# 5V_DCDC_XL7035.net
KiCad netlist of a schematic drawn in EAGLE
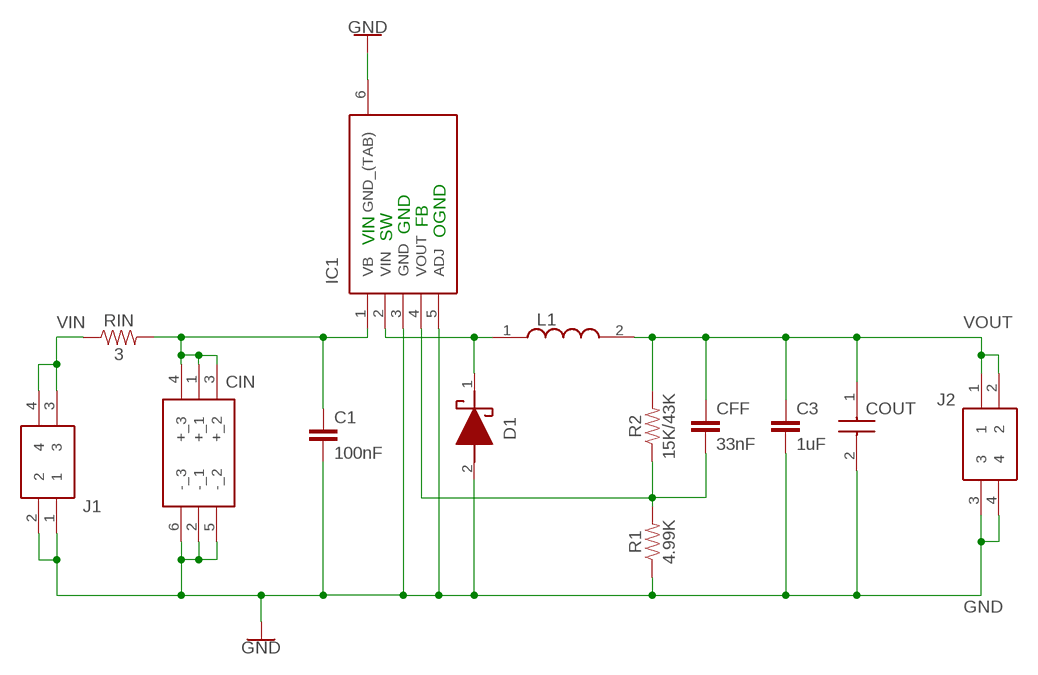
[diagram p0: schematic, sheet 1]

(export (version "E")
  (design (tool "Eeschema 10.0.6"))
  (components
    (comp (ref "C1")
      (value "100nF")
      (footprint "eagle-import:0603")
      (libsource (lib "eagle-import") (part "CAP-0603"))
    )
    (comp (ref "C3")
      (value "1uF")
      (footprint "eagle-import:0603")
      (libsource (lib "eagle-import") (part "CAP-0603"))
    )
    (comp (ref "CFF")
      (value "33nF")
      (footprint "eagle-import:0603")
      (libsource (lib "eagle-import") (part "CAP-0603"))
    )
    (comp (ref "CIN")
      (value "EEE-FK1K101AV")
      (footprint "eagle-import:EEEFK0J332AV")
      (fields (field (name "MOUSER_PART_NUMBER") "667-EEE-FK1K101AV"))
      (libsource (lib "eagle-import") (part "EEE-FK1K101AV"))
    )
    (comp (ref "COUT")
      (value "EMK325ABJ107MM-T")
      (footprint "eagle-import:CAPC3225X270N")
      (fields (field (name "MOUSER_PART_NUMBER") "963-EMK325ABJ107MM-T"))
      (libsource (lib "eagle-import") (part "EMK325ABJ107MM-T"))
    )
    (comp (ref "D1")
      (value "S310")
      (footprint "eagle-import:DIONM8059X265N")
      (fields (field (name "MOUSER_PART_NUMBER") "512-S310"))
      (libsource (lib "eagle-import") (part "S310"))
    )
    (comp (ref "IC1")
      (value "UC285TDKTTT-ADJ")
      (footprint "eagle-import:TO170P1524X483-6N")
      (fields (field (name "MOUSER_PART_NUMBER") "595-UC285TDKTTT-ADJ"))
      (libsource (lib "eagle-import") (part "UC285TDKTTT-ADJ"))
    )
    (comp (ref "J1")
      (value "691411510002")
      (footprint "eagle-import:691411510002")
      (fields (field (name "MOUSER_PART_NUMBER") "710-691411510002"))
      (libsource (lib "eagle-import") (part "691411510002"))
    )
    (comp (ref "J2")
      (value "691411510002")
      (footprint "eagle-import:691411510002")
      (fields (field (name "MOUSER_PART_NUMBER") "710-691411510002"))
      (libsource (lib "eagle-import") (part "691411510002"))
    )
    (comp (ref "L1")
      (value "SRR1280-101M")
      (footprint "eagle-import:INDPM125125X800N")
      (fields (field (name "MOUSER_PART_NUMBER") "652-SRR1280-101M"))
      (libsource (lib "eagle-import") (part "SRR1280-101M"))
    )
    (comp (ref "R1")
      (value "4.99K")
      (footprint "eagle-import:0603")
      (libsource (lib "eagle-import") (part "RESISTOR0603"))
    )
    (comp (ref "R2")
      (value "15K/43K")
      (footprint "eagle-import:0603")
      (libsource (lib "eagle-import") (part "RESISTOR0603"))
    )
    (comp (ref "RIN")
      (value "3")
      (footprint "eagle-import:1206")
      (libsource (lib "eagle-import") (part "RESISTOR1206"))
    )
  )
  (nets
    (net (code "1") (name "/VIN") (class "Default")
      (node (ref "J1") (pin "3") (pinfunction "3_3") (pintype "bidirectional"))
      (node (ref "J1") (pin "4") (pinfunction "4_4") (pintype "bidirectional"))
      (node (ref "RIN") (pin "1") (pinfunction "1_1") (pintype "passive"))
    )
    (net (code "2") (name "/VOUT") (class "Default")
      (node (ref "C3") (pin "1") (pinfunction "1_1") (pintype "passive"))
      (node (ref "CFF") (pin "1") (pinfunction "1_1") (pintype "passive"))
      (node (ref "COUT") (pin "1") (pinfunction "1_1") (pintype "bidirectional"))
      (node (ref "J2") (pin "1") (pinfunction "1_1") (pintype "bidirectional"))
      (node (ref "J2") (pin "2") (pinfunction "2_2") (pintype "bidirectional"))
      (node (ref "L1") (pin "2") (pinfunction "2_2") (pintype "bidirectional"))
      (node (ref "R2") (pin "2") (pinfunction "2_2") (pintype "passive"))
    )
    (net (code "3") (name "GND") (class "Default")
      (node (ref "C1") (pin "2") (pinfunction "2_2") (pintype "passive"))
      (node (ref "C3") (pin "2") (pinfunction "2_2") (pintype "passive"))
      (node (ref "CIN") (pin "2") (pinfunction "-_1_2") (pintype "bidirectional"))
      (node (ref "CIN") (pin "5") (pinfunction "-_2_5") (pintype "bidirectional"))
      (node (ref "CIN") (pin "6") (pinfunction "-_3_6") (pintype "bidirectional"))
      (node (ref "COUT") (pin "2") (pinfunction "2_2") (pintype "bidirectional"))
      (node (ref "D1") (pin "2") (pinfunction "A_2") (pintype "bidirectional"))
      (node (ref "IC1") (pin "3") (pinfunction "GND_3") (pintype "power_in"))
      (node (ref "IC1") (pin "5") (pinfunction "ADJ_5") (pintype "power_in"))
      (node (ref "IC1") (pin "6") (pinfunction "GND_(TAB)_6") (pintype "power_in"))
      (node (ref "J1") (pin "1") (pinfunction "1_1") (pintype "bidirectional"))
      (node (ref "J1") (pin "2") (pinfunction "2_2") (pintype "bidirectional"))
      (node (ref "J2") (pin "3") (pinfunction "3_3") (pintype "bidirectional"))
      (node (ref "J2") (pin "4") (pinfunction "4_4") (pintype "bidirectional"))
      (node (ref "R1") (pin "1") (pinfunction "1_1") (pintype "passive"))
    )
    (net (code "4") (name "Net-(CIN-+_1)") (class "Default")
      (node (ref "C1") (pin "1") (pinfunction "1_1") (pintype "passive"))
      (node (ref "CIN") (pin "1") (pinfunction "+_1_1") (pintype "bidirectional"))
      (node (ref "CIN") (pin "3") (pinfunction "+_2_3") (pintype "bidirectional"))
      (node (ref "CIN") (pin "4") (pinfunction "+_3_4") (pintype "bidirectional"))
      (node (ref "IC1") (pin "1") (pinfunction "VB_1") (pintype "bidirectional"))
      (node (ref "RIN") (pin "2") (pinfunction "2_2") (pintype "passive"))
    )
    (net (code "5") (name "Net-(D1-K)") (class "Default")
      (node (ref "D1") (pin "1") (pinfunction "K_1") (pintype "bidirectional"))
      (node (ref "IC1") (pin "2") (pinfunction "VIN_2") (pintype "output"))
      (node (ref "L1") (pin "1") (pinfunction "1_1") (pintype "bidirectional"))
    )
    (net (code "6") (name "Net-(IC1-VOUT)") (class "Default")
      (node (ref "CFF") (pin "2") (pinfunction "2_2") (pintype "passive"))
      (node (ref "IC1") (pin "4") (pinfunction "VOUT_4") (pintype "input"))
      (node (ref "R1") (pin "2") (pinfunction "2_2") (pintype "passive"))
      (node (ref "R2") (pin "1") (pinfunction "1_1") (pintype "passive"))
    )
  )
)
